# ADC_Zmatching.net
KiCad netlist of a schematic drawn in Altium Designer
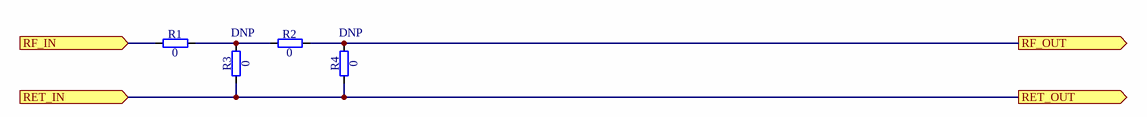
[diagram p0: ADC_Zmatching.SchDoc]

(export (version "E")
  (design (tool "Eeschema 10.0.6"))
  (components
    (comp (ref "R1")
      (value "0")
      (footprint "RESC1005X40N")
      (description "Resistor")
      (fields
        (field (name "PART NUMBER") "R0402_0R_JUMPER")
        (field (name "MANUFACTURER") "GENERIC")
        (field (name "AUTHOR") "CERN DEM JLC")
      )
      (libsource (lib "Resistors") (part "Resistor"))
    )
    (comp (ref "R2")
      (value "0")
      (footprint "RESC1005X40N")
      (description "Resistor")
      (fields
        (field (name "PART NUMBER") "R0402_0R_JUMPER")
        (field (name "MANUFACTURER") "GENERIC")
        (field (name "AUTHOR") "CERN DEM JLC")
      )
      (libsource (lib "Resistors") (part "Resistor"))
    )
    (comp (ref "R3")
      (value "0")
      (footprint "RESC1005X40N")
      (description "Resistor")
      (fields
        (field (name "PART NUMBER") "R0402_0R_JUMPER")
        (field (name "MANUFACTURER") "GENERIC")
        (field (name "MOUNTED") "DNP")
        (field (name "AUTHOR") "CERN DEM JLC")
      )
      (libsource (lib "Resistors") (part "Resistor"))
    )
    (comp (ref "R4")
      (value "0")
      (footprint "RESC1005X40N")
      (description "Resistor")
      (fields
        (field (name "PART NUMBER") "R0402_0R_JUMPER")
        (field (name "MANUFACTURER") "GENERIC")
        (field (name "MOUNTED") "DNP")
        (field (name "AUTHOR") "CERN DEM JLC")
      )
      (libsource (lib "Resistors") (part "Resistor"))
    )
  )
  (nets
    (net (code "1") (name "/RET_IN") (class "Default")
      (node (ref "R3") (pin "1") (pinfunction "1_1") (pintype "passive"))
      (node (ref "R4") (pin "1") (pinfunction "1_1") (pintype "passive"))
    )
    (net (code "2") (name "/RF_IN") (class "Default")
      (node (ref "R1") (pin "1") (pinfunction "1_1") (pintype "passive"))
    )
    (net (code "3") (name "/RF_OUT") (class "Default")
      (node (ref "R2") (pin "2") (pinfunction "2_2") (pintype "passive"))
      (node (ref "R4") (pin "2") (pinfunction "2_2") (pintype "passive"))
    )
    (net (code "4") (name "Net-(R1-Pad2)") (class "Default")
      (node (ref "R1") (pin "2") (pinfunction "2_2") (pintype "passive"))
      (node (ref "R2") (pin "1") (pinfunction "1_1") (pintype "passive"))
      (node (ref "R3") (pin "2") (pinfunction "2_2") (pintype "passive"))
    )
  )
)
